# SensorShield-Smoke.net
KiCad netlist of a schematic drawn in EAGLE
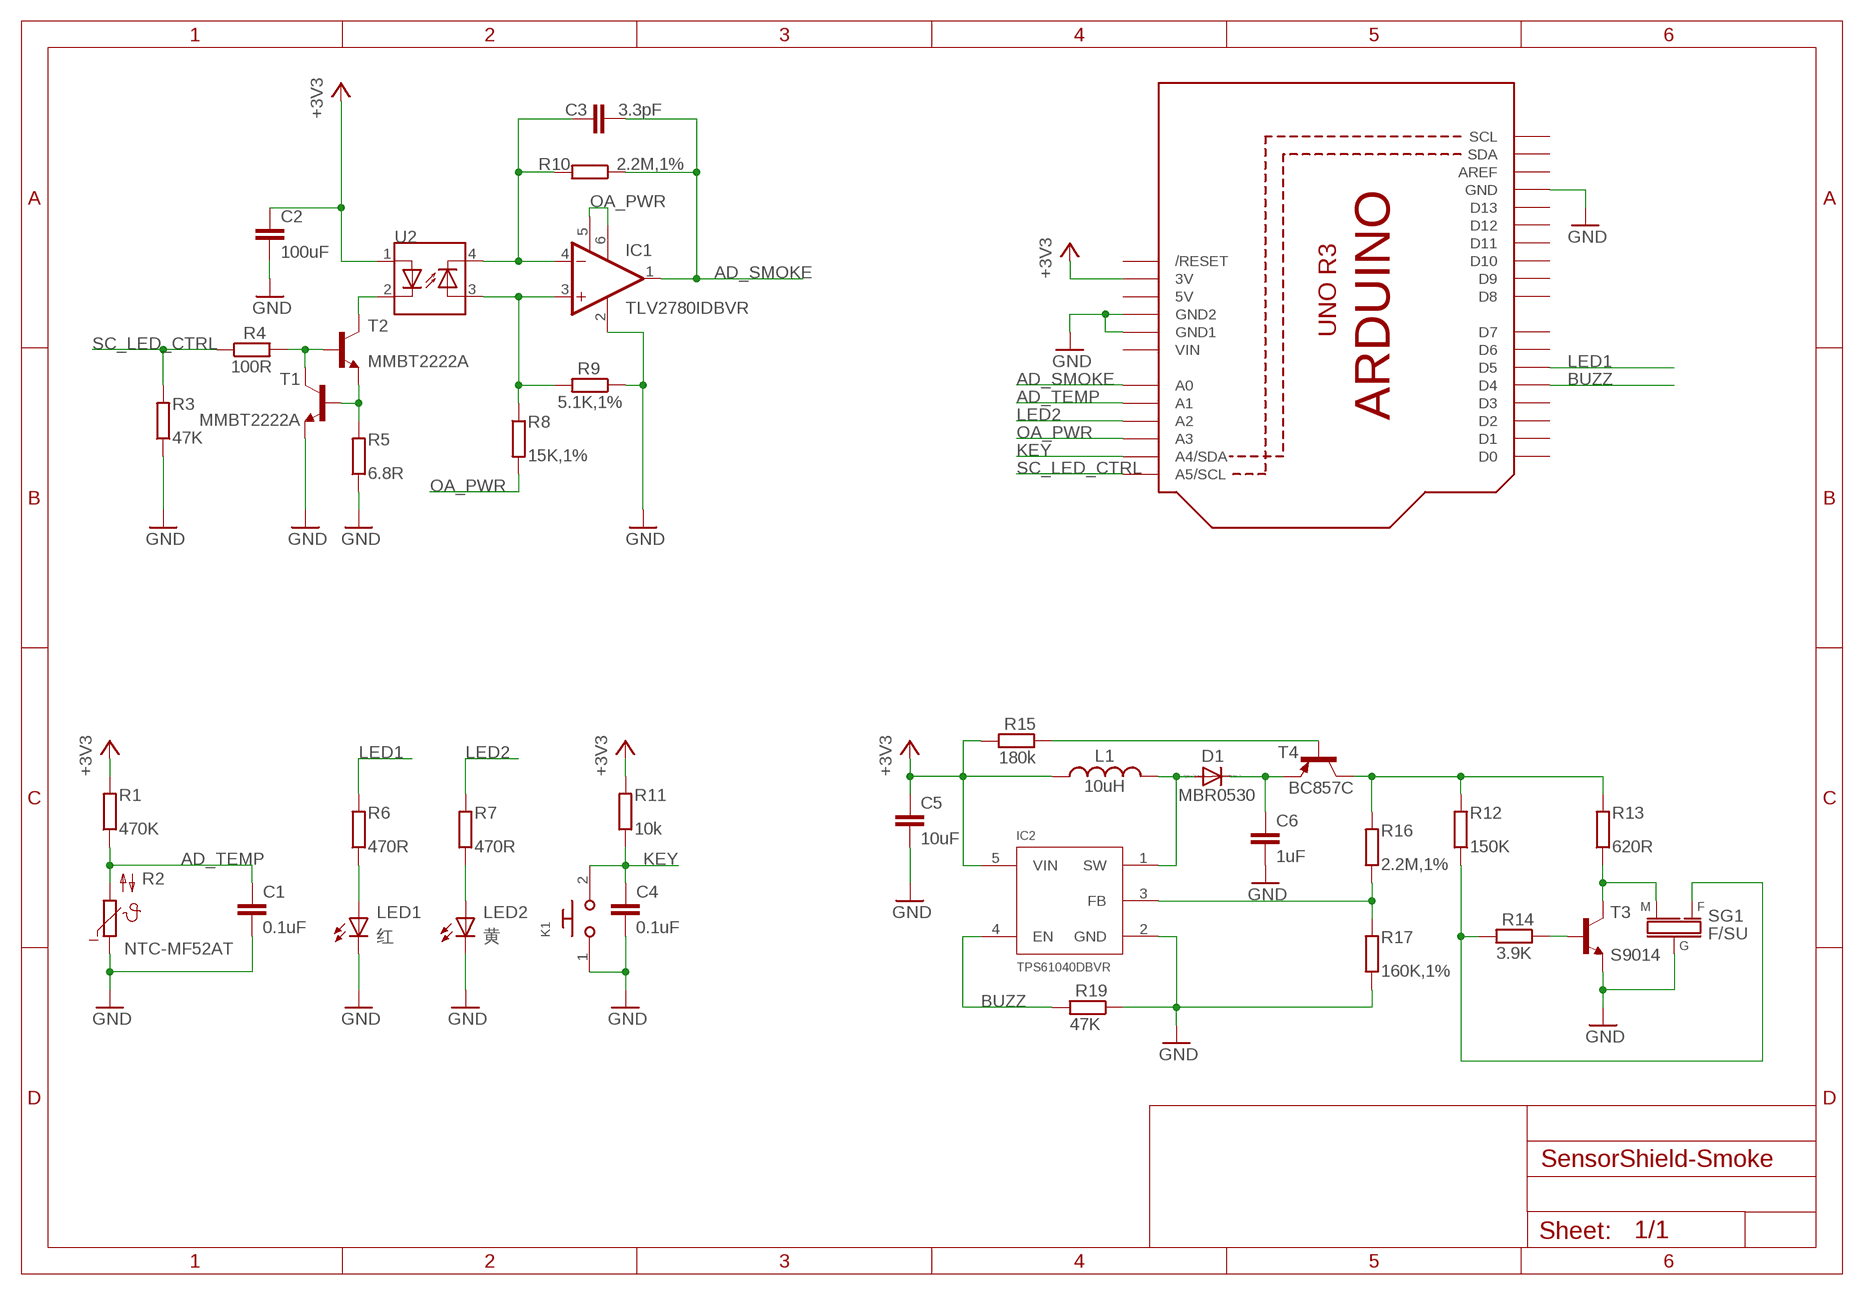
[diagram p0: schematic, sheet 1]

(export (version "E")
  (design (tool "Eeschema 10.0.6"))
  (components
    (comp (ref "C1")
      (value "0.1uF")
      (footprint "eagle-import:C0805")
      (libsource (lib "eagle-import") (part "C-EUC0805"))
    )
    (comp (ref "C2")
      (value "100uF")
      (footprint "eagle-import:C1210")
      (libsource (lib "eagle-import") (part "C-EUC1210"))
    )
    (comp (ref "C3")
      (value "3.3pF")
      (footprint "eagle-import:C0805")
      (libsource (lib "eagle-import") (part "C-EUC0805"))
    )
    (comp (ref "C4")
      (value "0.1uF")
      (footprint "eagle-import:C0805")
      (libsource (lib "eagle-import") (part "C-EUC0805"))
    )
    (comp (ref "C5")
      (value "10uF")
      (footprint "eagle-import:C0805")
      (libsource (lib "eagle-import") (part "C-EUC0805"))
    )
    (comp (ref "C6")
      (value "1uF")
      (footprint "eagle-import:C0805")
      (libsource (lib "eagle-import") (part "C-EUC0805"))
    )
    (comp (ref "D1")
      (value "MBR0530")
      (footprint "eagle-import:SOD123")
      (libsource (lib "eagle-import") (part "DIODE-SOD123"))
    )
    (comp (ref "IC1")
      (value "TLV2780IDBVR")
      (footprint "eagle-import:SOT23-6")
      (libsource (lib "eagle-import") (part "TLV2780IDBVR"))
    )
    (comp (ref "IC2")
      (value "TPS61040DBVR")
      (footprint "eagle-import:DBV0005A")
      (fields (field (name "MANUFACTURER") "Texas Instruments"))
      (libsource (lib "eagle-import") (part "TPS61040DBVR"))
    )
    (comp (ref "K1")
      (value "MYLIBRARY_MICRO_SWITCH")
      (footprint "eagle-import:MYLIBRARY_MICROSWITCH")
      (libsource (lib "eagle-import") (part "MYLIBRARY_MICRO_SWITCH"))
    )
    (comp (ref "L1")
      (value "10uH")
      (footprint "eagle-import:L3216C")
      (libsource (lib "eagle-import") (part "L-USL3216C"))
    )
    (comp (ref "LED1")
      (value "红")
      (footprint "eagle-import:SML0805")
      (libsource (lib "eagle-import") (part "LEDSML0805"))
    )
    (comp (ref "LED2")
      (value "黄")
      (footprint "eagle-import:SML0805")
      (libsource (lib "eagle-import") (part "LEDSML0805"))
    )
    (comp (ref "Q1")
      (value "ARDUINOR3-NOIOREF-NOTEXT")
      (footprint "eagle-import:ARDUINOR3-NOTEXT-NOIOREF")
      (libsource (lib "eagle-import") (part "ARDUINOR3-NOIOREF-NOTEXT"))
    )
    (comp (ref "R1")
      (value "470K")
      (footprint "eagle-import:R0805")
      (libsource (lib "eagle-import") (part "R-EU_R0805"))
    )
    (comp (ref "R2")
      (value "NTC-MF52AT")
      (footprint "eagle-import:P640")
      (libsource (lib "eagle-import") (part "NTC640"))
    )
    (comp (ref "R3")
      (value "47K")
      (footprint "eagle-import:R0805")
      (libsource (lib "eagle-import") (part "R-EU_R0805"))
    )
    (comp (ref "R4")
      (value "100R")
      (footprint "eagle-import:R0805")
      (libsource (lib "eagle-import") (part "R-EU_R0805"))
    )
    (comp (ref "R5")
      (value "6.8R")
      (footprint "eagle-import:R0805")
      (libsource (lib "eagle-import") (part "R-EU_R0805"))
    )
    (comp (ref "R6")
      (value "470R")
      (footprint "eagle-import:R0805")
      (libsource (lib "eagle-import") (part "R-EU_R0805"))
    )
    (comp (ref "R7")
      (value "470R")
      (footprint "eagle-import:R0805")
      (libsource (lib "eagle-import") (part "R-EU_R0805"))
    )
    (comp (ref "R8")
      (value "15K,1%")
      (footprint "eagle-import:R0805")
      (libsource (lib "eagle-import") (part "R-EU_R0805"))
    )
    (comp (ref "R9")
      (value "5.1K,1%")
      (footprint "eagle-import:R0805")
      (libsource (lib "eagle-import") (part "R-EU_R0805"))
    )
    (comp (ref "R10")
      (value "2.2M,1%")
      (footprint "eagle-import:R0805")
      (libsource (lib "eagle-import") (part "R-EU_R0805"))
    )
    (comp (ref "R11")
      (value "10k")
      (footprint "eagle-import:R0805")
      (libsource (lib "eagle-import") (part "R-EU_R0805"))
    )
    (comp (ref "R12")
      (value "150K")
      (footprint "eagle-import:R0805")
      (libsource (lib "eagle-import") (part "R-EU_R0805"))
    )
    (comp (ref "R13")
      (value "620R")
      (footprint "eagle-import:R0805")
      (libsource (lib "eagle-import") (part "R-EU_R0805"))
    )
    (comp (ref "R14")
      (value "3.9K")
      (footprint "eagle-import:R0805")
      (libsource (lib "eagle-import") (part "R-EU_R0805"))
    )
    (comp (ref "R15")
      (value "180k")
      (footprint "eagle-import:R0805")
      (libsource (lib "eagle-import") (part "R-EU_R0805"))
    )
    (comp (ref "R16")
      (value "2.2M,1%")
      (footprint "eagle-import:R0805")
      (libsource (lib "eagle-import") (part "R-EU_R0805"))
    )
    (comp (ref "R17")
      (value "160K,1%")
      (footprint "eagle-import:R0805")
      (libsource (lib "eagle-import") (part "R-EU_R0805"))
    )
    (comp (ref "R19")
      (value "47K")
      (footprint "eagle-import:R0805")
      (libsource (lib "eagle-import") (part "R-EU_R0805"))
    )
    (comp (ref "SG1")
      (value "F/SU")
      (footprint "eagle-import:F_SU")
      (libsource (lib "eagle-import") (part "F/SU"))
    )
    (comp (ref "T1")
      (value "MMBT2222A")
      (footprint "eagle-import:SOT23-BEC")
      (libsource (lib "eagle-import") (part "-NPN-SOT23-BECMMBT2222ALT1"))
    )
    (comp (ref "T2")
      (value "MMBT2222A")
      (footprint "eagle-import:SOT23-BEC")
      (libsource (lib "eagle-import") (part "-NPN-SOT23-BECMMBT2222ALT1"))
    )
    (comp (ref "T3")
      (value "S9014")
      (footprint "eagle-import:SOT23-BEC")
      (libsource (lib "eagle-import") (part "-NPN-SOT23-BECBC847C"))
    )
    (comp (ref "T4")
      (value "BC857C")
      (footprint "eagle-import:SOT23-BEC")
      (libsource (lib "eagle-import") (part "-PNP-SOT23-BECBC857C"))
    )
    (comp (ref "U2")
      (value "SMOKE-CHAMBER6-131")
      (footprint "eagle-import:6-131")
      (libsource (lib "eagle-import") (part "SMOKE-CHAMBER6-131"))
    )
  )
  (nets
    (net (code "1") (name "+3V3") (class "Default")
      (node (ref "C2") (pin "1") (pinfunction "1_1") (pintype "passive"))
      (node (ref "C5") (pin "1") (pinfunction "1_1") (pintype "passive"))
      (node (ref "IC2") (pin "5") (pinfunction "VIN_5") (pintype "power_in"))
      (node (ref "L1") (pin "1") (pinfunction "1_1") (pintype "passive"))
      (node (ref "Q1") (pin "3V") (pinfunction "3V_3V") (pintype "power_in"))
      (node (ref "R1") (pin "2") (pinfunction "2_2") (pintype "passive"))
      (node (ref "R11") (pin "2") (pinfunction "2_2") (pintype "passive"))
      (node (ref "R15") (pin "2") (pinfunction "2_2") (pintype "passive"))
      (node (ref "U2") (pin "1") (pinfunction "A_1") (pintype "passive"))
    )
    (net (code "2") (name "/5V") (class "Default")
      (node (ref "Q1") (pin "5V") (pinfunction "5V_5V") (pintype "power_in"))
    )
    (net (code "3") (name "/AD_SMOKE") (class "Default")
      (node (ref "C3") (pin "1") (pinfunction "1_1") (pintype "passive"))
      (node (ref "IC1") (pin "1") (pinfunction "OUT_1") (pintype "output"))
      (node (ref "Q1") (pin "A0") (pinfunction "A0_A0") (pintype "bidirectional"))
      (node (ref "R10") (pin "1") (pinfunction "1_1") (pintype "passive"))
    )
    (net (code "4") (name "/AD_TEMP") (class "Default")
      (node (ref "C1") (pin "1") (pinfunction "1_1") (pintype "passive"))
      (node (ref "Q1") (pin "A1") (pinfunction "A1_A1") (pintype "bidirectional"))
      (node (ref "R1") (pin "1") (pinfunction "1_1") (pintype "passive"))
      (node (ref "R2") (pin "2") (pinfunction "2_2") (pintype "passive"))
    )
    (net (code "5") (name "/BUZZ") (class "Default")
      (node (ref "IC2") (pin "4") (pinfunction "EN_4") (pintype "input"))
      (node (ref "Q1") (pin "D4") (pinfunction "D4_D4") (pintype "bidirectional"))
      (node (ref "R19") (pin "2") (pinfunction "2_2") (pintype "passive"))
    )
    (net (code "6") (name "/KEY") (class "Default")
      (node (ref "C4") (pin "1") (pinfunction "1_1") (pintype "passive"))
      (node (ref "K1") (pin "2") (pinfunction "2_2") (pintype "bidirectional"))
      (node (ref "Q1") (pin "A4") (pinfunction "A4/SDA_A4") (pintype "bidirectional"))
      (node (ref "R11") (pin "1") (pinfunction "1_1") (pintype "passive"))
    )
    (net (code "7") (name "/LED1") (class "Default")
      (node (ref "Q1") (pin "D5") (pinfunction "D5_D5") (pintype "bidirectional"))
      (node (ref "R6") (pin "2") (pinfunction "2_2") (pintype "passive"))
    )
    (net (code "8") (name "/LED2") (class "Default")
      (node (ref "Q1") (pin "A2") (pinfunction "A2_A2") (pintype "bidirectional"))
      (node (ref "R7") (pin "2") (pinfunction "2_2") (pintype "passive"))
    )
    (net (code "9") (name "/OA_PWR") (class "Default")
      (node (ref "IC1") (pin "5") (pinfunction "~{SHDN}_5") (pintype "bidirectional"))
      (node (ref "IC1") (pin "6") (pinfunction "V+_6") (pintype "power_in"))
      (node (ref "Q1") (pin "A3") (pinfunction "A3_A3") (pintype "bidirectional"))
      (node (ref "R8") (pin "2") (pinfunction "2_2") (pintype "passive"))
    )
    (net (code "10") (name "/SC_LED_CTRL") (class "Default")
      (node (ref "Q1") (pin "A5") (pinfunction "A5/SCL_A5") (pintype "bidirectional"))
      (node (ref "R3") (pin "2") (pinfunction "2_2") (pintype "passive"))
      (node (ref "R4") (pin "1") (pinfunction "1_1") (pintype "passive"))
    )
    (net (code "11") (name "/VIN") (class "Default")
      (node (ref "Q1") (pin "VIN") (pinfunction "VIN_VIN") (pintype "power_in"))
    )
    (net (code "12") (name "GND") (class "Default")
      (node (ref "C1") (pin "2") (pinfunction "2_2") (pintype "passive"))
      (node (ref "C2") (pin "2") (pinfunction "2_2") (pintype "passive"))
      (node (ref "C4") (pin "2") (pinfunction "2_2") (pintype "passive"))
      (node (ref "C5") (pin "2") (pinfunction "2_2") (pintype "passive"))
      (node (ref "C6") (pin "2") (pinfunction "2_2") (pintype "passive"))
      (node (ref "IC1") (pin "2") (pinfunction "V-_2") (pintype "power_in"))
      (node (ref "IC2") (pin "2") (pinfunction "GND_2") (pintype "power_in"))
      (node (ref "K1") (pin "1") (pinfunction "1_1") (pintype "bidirectional"))
      (node (ref "LED1") (pin "C") (pinfunction "C_C") (pintype "passive"))
      (node (ref "LED2") (pin "C") (pinfunction "C_C") (pintype "passive"))
      (node (ref "Q1") (pin "GND") (pinfunction "GND_GND") (pintype "power_in"))
      (node (ref "Q1") (pin "GND1") (pinfunction "GND1_GND1") (pintype "power_in"))
      (node (ref "Q1") (pin "GND2") (pinfunction "GND2_GND2") (pintype "power_in"))
      (node (ref "R17") (pin "1") (pinfunction "1_1") (pintype "passive"))
      (node (ref "R19") (pin "1") (pinfunction "1_1") (pintype "passive"))
      (node (ref "R2") (pin "1") (pinfunction "1_1") (pintype "passive"))
      (node (ref "R3") (pin "1") (pinfunction "1_1") (pintype "passive"))
      (node (ref "R5") (pin "1") (pinfunction "1_1") (pintype "passive"))
      (node (ref "R9") (pin "1") (pinfunction "1_1") (pintype "passive"))
      (node (ref "SG1") (pin "3") (pinfunction "G_3") (pintype "passive"))
      (node (ref "T1") (pin "E") (pinfunction "E_E") (pintype "passive"))
      (node (ref "T3") (pin "E") (pinfunction "E_E") (pintype "passive"))
    )
    (net (code "13") (name "Net-(C6-Pad1)") (class "Default")
      (node (ref "C6") (pin "1") (pinfunction "1_1") (pintype "passive"))
      (node (ref "D1") (pin "C") (pinfunction "C_C") (pintype "passive"))
      (node (ref "T4") (pin "E") (pinfunction "E_E") (pintype "passive"))
    )
    (net (code "14") (name "Net-(IC1A-+IN)") (class "Default")
      (node (ref "IC1") (pin "3") (pinfunction "+IN_3") (pintype "input"))
      (node (ref "R8") (pin "1") (pinfunction "1_1") (pintype "passive"))
      (node (ref "R9") (pin "2") (pinfunction "2_2") (pintype "passive"))
      (node (ref "U2") (pin "3") (pinfunction "A1_3") (pintype "passive"))
    )
    (net (code "15") (name "Net-(IC1A--IN)") (class "Default")
      (node (ref "C3") (pin "2") (pinfunction "2_2") (pintype "passive"))
      (node (ref "IC1") (pin "4") (pinfunction "-IN_4") (pintype "input"))
      (node (ref "R10") (pin "2") (pinfunction "2_2") (pintype "passive"))
      (node (ref "U2") (pin "4") (pinfunction "C1_4") (pintype "passive"))
    )
    (net (code "16") (name "Net-(IC2-FB)") (class "Default")
      (node (ref "IC2") (pin "3") (pinfunction "FB_3") (pintype "input"))
      (node (ref "R16") (pin "1") (pinfunction "1_1") (pintype "passive"))
      (node (ref "R17") (pin "2") (pinfunction "2_2") (pintype "passive"))
    )
    (net (code "17") (name "Net-(IC2-SW)") (class "Default")
      (node (ref "D1") (pin "A") (pinfunction "A_A") (pintype "passive"))
      (node (ref "IC2") (pin "1") (pinfunction "SW_1") (pintype "power_in"))
      (node (ref "L1") (pin "2") (pinfunction "2_2") (pintype "passive"))
    )
    (net (code "18") (name "Net-(LED1-PadA)") (class "Default")
      (node (ref "LED1") (pin "A") (pinfunction "A_A") (pintype "passive"))
      (node (ref "R6") (pin "1") (pinfunction "1_1") (pintype "passive"))
    )
    (net (code "19") (name "Net-(LED2-PadA)") (class "Default")
      (node (ref "LED2") (pin "A") (pinfunction "A_A") (pintype "passive"))
      (node (ref "R7") (pin "1") (pinfunction "1_1") (pintype "passive"))
    )
    (net (code "20") (name "Net-(R4-Pad2)") (class "Default")
      (node (ref "R4") (pin "2") (pinfunction "2_2") (pintype "passive"))
      (node (ref "T1") (pin "C") (pinfunction "C_C") (pintype "passive"))
      (node (ref "T2") (pin "B") (pinfunction "B_B") (pintype "passive"))
    )
    (net (code "21") (name "Net-(R5-Pad2)") (class "Default")
      (node (ref "R5") (pin "2") (pinfunction "2_2") (pintype "passive"))
      (node (ref "T1") (pin "B") (pinfunction "B_B") (pintype "passive"))
      (node (ref "T2") (pin "E") (pinfunction "E_E") (pintype "passive"))
    )
    (net (code "22") (name "Net-(R12-Pad2)") (class "Default")
      (node (ref "R12") (pin "2") (pinfunction "2_2") (pintype "passive"))
      (node (ref "R13") (pin "2") (pinfunction "2_2") (pintype "passive"))
      (node (ref "R16") (pin "2") (pinfunction "2_2") (pintype "passive"))
      (node (ref "T4") (pin "C") (pinfunction "C_C") (pintype "passive"))
    )
    (net (code "23") (name "Net-(R14-Pad1)") (class "Default")
      (node (ref "R14") (pin "1") (pinfunction "1_1") (pintype "passive"))
      (node (ref "T3") (pin "B") (pinfunction "B_B") (pintype "passive"))
    )
    (net (code "24") (name "Net-(R15-Pad1)") (class "Default")
      (node (ref "R15") (pin "1") (pinfunction "1_1") (pintype "passive"))
      (node (ref "T4") (pin "B") (pinfunction "B_B") (pintype "passive"))
    )
    (net (code "25") (name "Net-(SG1-F)") (class "Default")
      (node (ref "R12") (pin "1") (pinfunction "1_1") (pintype "passive"))
      (node (ref "R14") (pin "2") (pinfunction "2_2") (pintype "passive"))
      (node (ref "SG1") (pin "1") (pinfunction "F_1") (pintype "passive"))
    )
    (net (code "26") (name "Net-(SG1-M)") (class "Default")
      (node (ref "R13") (pin "1") (pinfunction "1_1") (pintype "passive"))
      (node (ref "SG1") (pin "2") (pinfunction "M_2") (pintype "passive"))
      (node (ref "T3") (pin "C") (pinfunction "C_C") (pintype "passive"))
    )
    (net (code "27") (name "Net-(U2-C)") (class "Default")
      (node (ref "T2") (pin "C") (pinfunction "C_C") (pintype "passive"))
      (node (ref "U2") (pin "2") (pinfunction "C_2") (pintype "passive"))
    )
    (net (code "28") (name "unconnected-(Q1-PadAREF)") (class "Default")
      (node (ref "Q1") (pin "AREF") (pinfunction "AREF_AREF") (pintype "bidirectional"))
    )
    (net (code "29") (name "unconnected-(Q1-PadD0)") (class "Default")
      (node (ref "Q1") (pin "D0") (pinfunction "D0_D0") (pintype "bidirectional"))
    )
    (net (code "30") (name "unconnected-(Q1-PadD1)") (class "Default")
      (node (ref "Q1") (pin "D1") (pinfunction "D1_D1") (pintype "bidirectional"))
    )
    (net (code "31") (name "unconnected-(Q1-PadD2)") (class "Default")
      (node (ref "Q1") (pin "D2") (pinfunction "D2_D2") (pintype "bidirectional"))
    )
    (net (code "32") (name "unconnected-(Q1-PadD3)") (class "Default")
      (node (ref "Q1") (pin "D3") (pinfunction "D3_D3") (pintype "bidirectional"))
    )
    (net (code "33") (name "unconnected-(Q1-PadD6)") (class "Default")
      (node (ref "Q1") (pin "D6") (pinfunction "D6_D6") (pintype "bidirectional"))
    )
    (net (code "34") (name "unconnected-(Q1-PadD7)") (class "Default")
      (node (ref "Q1") (pin "D7") (pinfunction "D7_D7") (pintype "bidirectional"))
    )
    (net (code "35") (name "unconnected-(Q1-PadD8)") (class "Default")
      (node (ref "Q1") (pin "D8") (pinfunction "D8_D8") (pintype "bidirectional"))
    )
    (net (code "36") (name "unconnected-(Q1-PadD9)") (class "Default")
      (node (ref "Q1") (pin "D9") (pinfunction "D9_D9") (pintype "bidirectional"))
    )
    (net (code "37") (name "unconnected-(Q1-PadD10)") (class "Default")
      (node (ref "Q1") (pin "D10") (pinfunction "D10_D10") (pintype "bidirectional"))
    )
    (net (code "38") (name "unconnected-(Q1-PadD11)") (class "Default")
      (node (ref "Q1") (pin "D11") (pinfunction "D11_D11") (pintype "bidirectional"))
    )
    (net (code "39") (name "unconnected-(Q1-PadD12)") (class "Default")
      (node (ref "Q1") (pin "D12") (pinfunction "D12_D12") (pintype "bidirectional"))
    )
    (net (code "40") (name "unconnected-(Q1-PadD13)") (class "Default")
      (node (ref "Q1") (pin "D13") (pinfunction "D13_D13") (pintype "bidirectional"))
    )
    (net (code "41") (name "unconnected-(Q1-PadSCL)") (class "Default")
      (node (ref "Q1") (pin "SCL") (pinfunction "SCL_SCL") (pintype "bidirectional"))
    )
    (net (code "42") (name "unconnected-(Q1-PadSDA)") (class "Default")
      (node (ref "Q1") (pin "SDA") (pinfunction "SDA_SDA") (pintype "bidirectional"))
    )
    (net (code "43") (name "unconnected-(Q1-{slash}RESET-PadRESET)") (class "Default")
      (node (ref "Q1") (pin "RESET") (pinfunction "/RESET_RESET") (pintype "bidirectional"))
    )
  )
)
